# ScoutMakes_FM_Kit.net
KiCad netlist of a schematic drawn in EAGLE
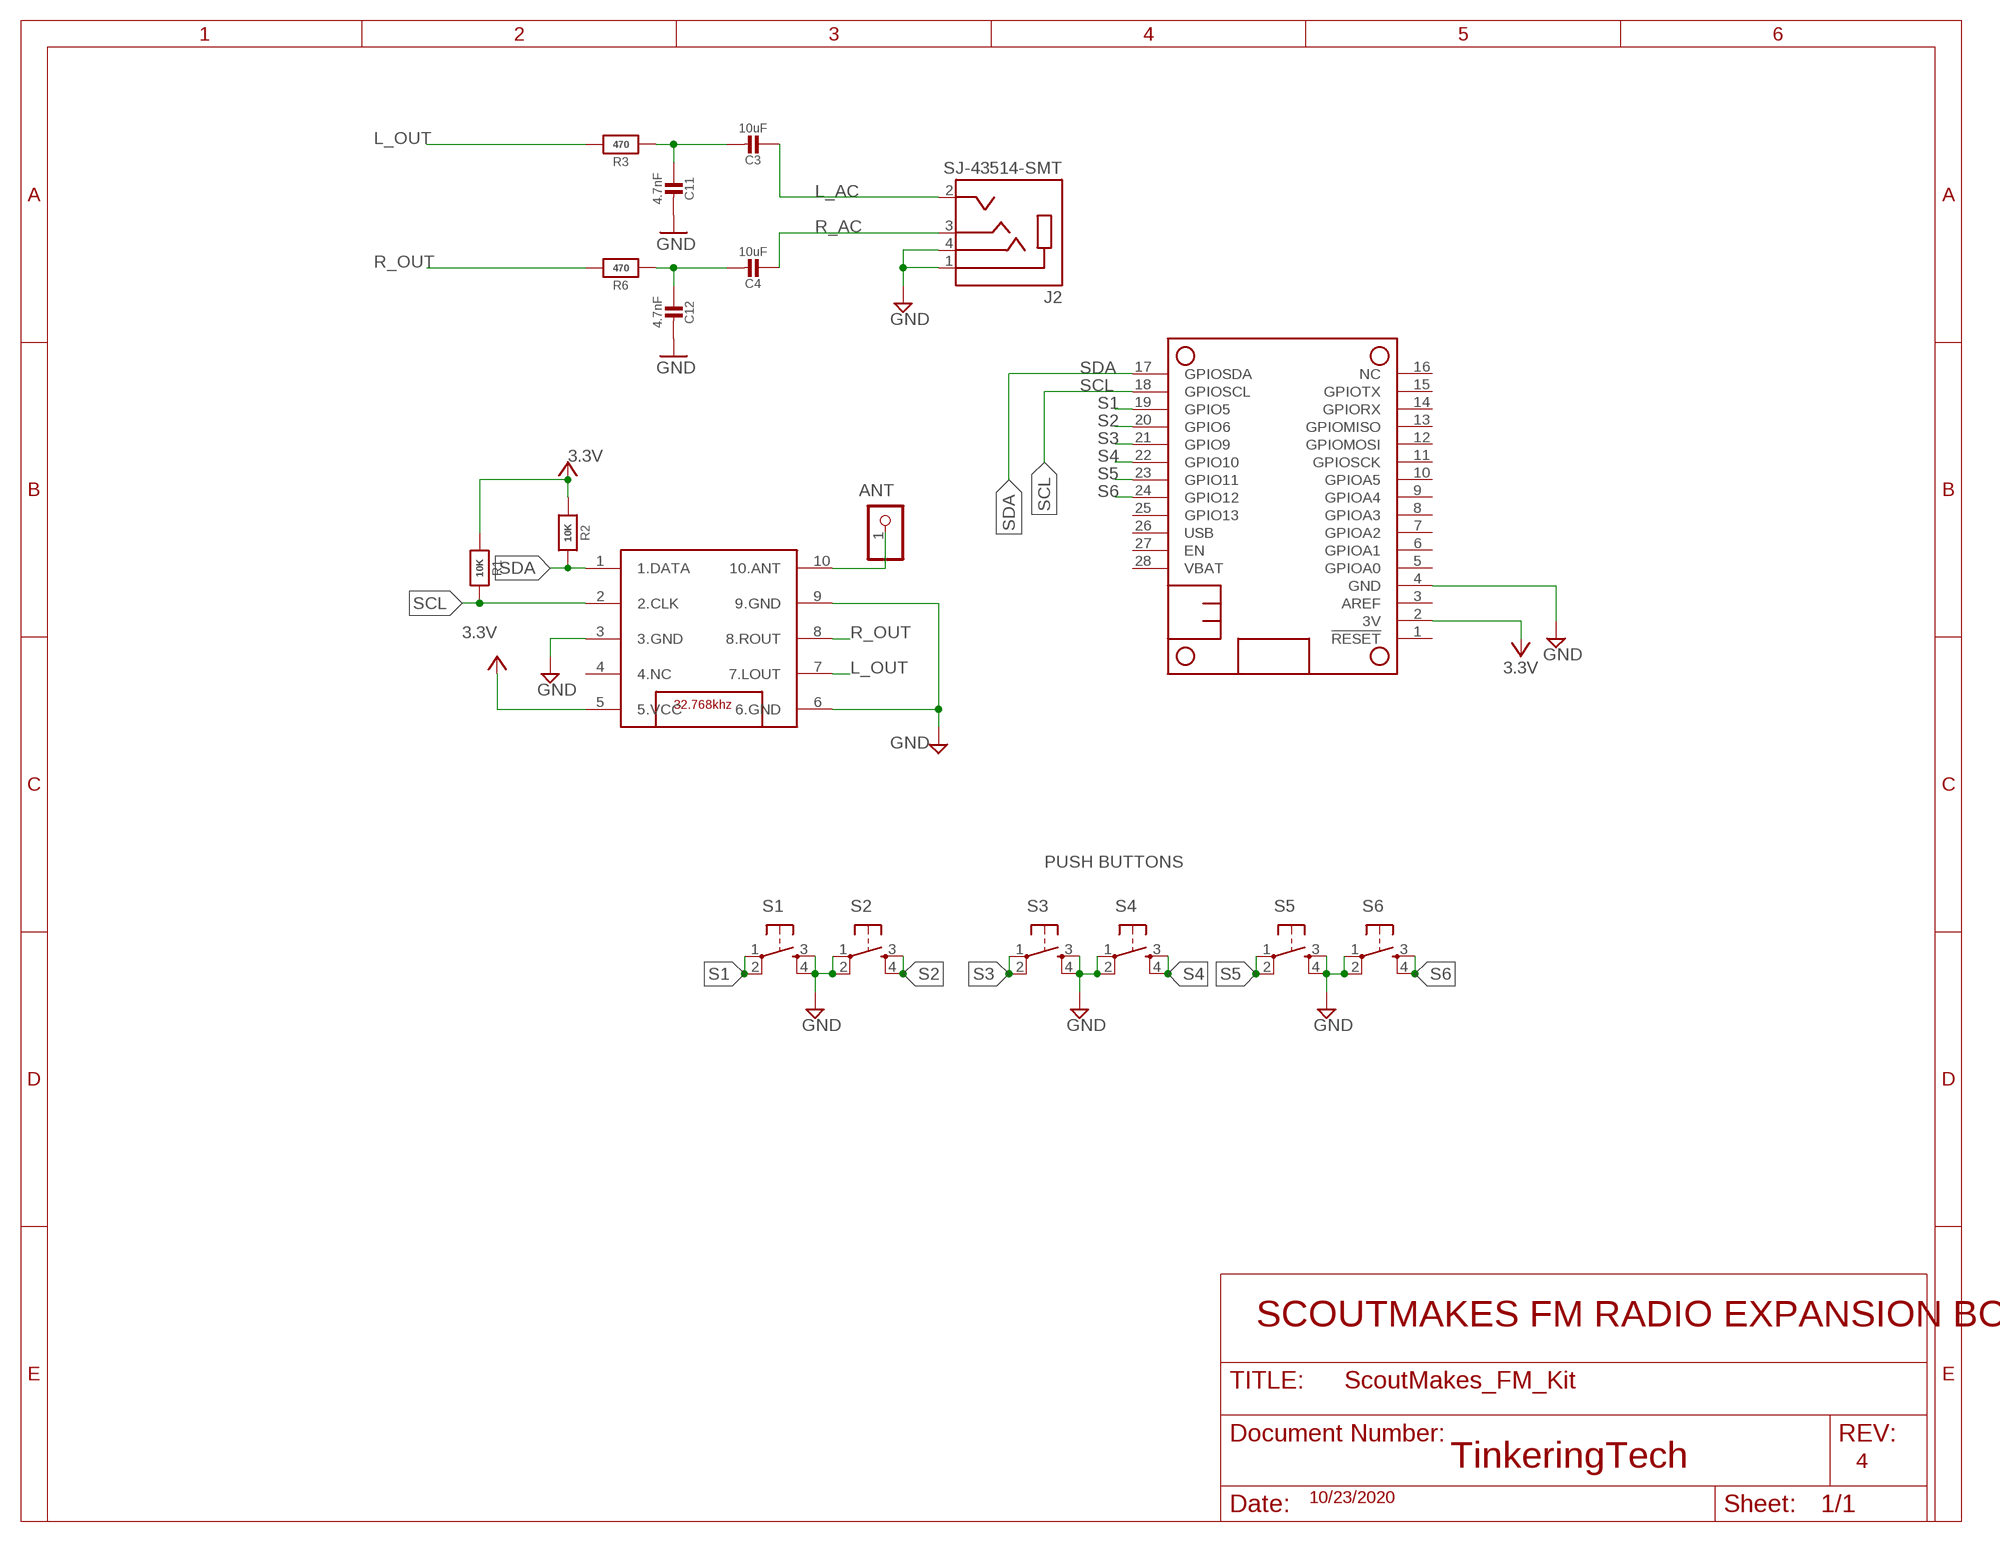
[diagram p0: schematic, sheet 1]

(export (version "E")
  (design (tool "Eeschema 10.0.6"))
  (components
    (comp (ref "ANT")
      (value "PINHD-1X1")
      (footprint "eagle-import:1X01")
      (libsource (lib "eagle-import") (part "PINHD-1X1"))
    )
    (comp (ref "C3")
      (value "10uF")
      (footprint "eagle-import:0805-NO")
      (libsource (lib "eagle-import") (part "CAP_CERAMIC0805-NOOUTLINE"))
    )
    (comp (ref "C4")
      (value "10uF")
      (footprint "eagle-import:0805-NO")
      (libsource (lib "eagle-import") (part "CAP_CERAMIC0805-NOOUTLINE"))
    )
    (comp (ref "C11")
      (value "4.7nF")
      (footprint "eagle-import:0805-NO")
      (libsource (lib "eagle-import") (part "CAP_CERAMIC0805-NOOUTLINE"))
    )
    (comp (ref "C12")
      (value "4.7nF")
      (footprint "eagle-import:0805-NO")
      (libsource (lib "eagle-import") (part "CAP_CERAMIC0805-NOOUTLINE"))
    )
    (comp (ref "J2")
      (value "SJ-43514-SMT")
      (footprint "eagle-import:CUI_SJ-43514-SMT")
      (fields
        (field (name "DIGI-KEY_PART_NUMBER") "CP-43514SJCT-ND")
        (field (name "MF") "CUI Devices")
        (field (name "MP") "SJ-43514-SMT-TR")
      )
      (libsource (lib "eagle-import") (part "SJ-43514-SMT"))
    )
    (comp (ref "MS2")
      (value "FEATHERWING_NODIM")
      (footprint "eagle-import:FEATHERWING_DIM")
      (libsource (lib "eagle-import") (part "FEATHERWING_NODIM"))
    )
    (comp (ref "R1")
      (value "10K")
      (footprint "eagle-import:0603-NO")
      (libsource (lib "eagle-import") (part "RESISTOR_0603_NOOUT"))
    )
    (comp (ref "R2")
      (value "10K")
      (footprint "eagle-import:0603-NO")
      (libsource (lib "eagle-import") (part "RESISTOR_0603_NOOUT"))
    )
    (comp (ref "R3")
      (value "470")
      (footprint "eagle-import:0805-NO")
      (libsource (lib "eagle-import") (part "RESISTOR0805_NOOUTLINE"))
    )
    (comp (ref "R6")
      (value "470")
      (footprint "eagle-import:0805-NO")
      (libsource (lib "eagle-import") (part "RESISTOR0805_NOOUTLINE"))
    )
    (comp (ref "S1")
      (value "DTS-6")
      (footprint "eagle-import:DTS-6")
      (libsource (lib "eagle-import") (part "DTS-6"))
    )
    (comp (ref "S2")
      (value "DTS-6")
      (footprint "eagle-import:DTS-6")
      (libsource (lib "eagle-import") (part "DTS-6"))
    )
    (comp (ref "S3")
      (value "DTS-6")
      (footprint "eagle-import:DTS-6")
      (libsource (lib "eagle-import") (part "DTS-6"))
    )
    (comp (ref "S4")
      (value "DTS-6")
      (footprint "eagle-import:DTS-6")
      (libsource (lib "eagle-import") (part "DTS-6"))
    )
    (comp (ref "S5")
      (value "DTS-6")
      (footprint "eagle-import:DTS-6")
      (libsource (lib "eagle-import") (part "DTS-6"))
    )
    (comp (ref "S6")
      (value "DTS-6")
      (footprint "eagle-import:DTS-6")
      (libsource (lib "eagle-import") (part "DTS-6"))
    )
    (comp (ref "U1")
      (value "TEA5767")
      (footprint "eagle-import:TJ-102BC")
      (libsource (lib "eagle-import") (part "TEA5767"))
    )
  )
  (nets
    (net (code "1") (name "/L_AC") (class "Default")
      (node (ref "C3") (pin "1") (pinfunction "1_1") (pintype "passive"))
      (node (ref "J2") (pin "2") (pinfunction "TIP_2") (pintype "passive"))
    )
    (net (code "2") (name "/L_OUT") (class "Default")
      (node (ref "R3") (pin "1") (pinfunction "1_1") (pintype "passive"))
      (node (ref "U1") (pin "7") (pinfunction "7.LOUT_7") (pintype "bidirectional"))
    )
    (net (code "3") (name "/R_AC") (class "Default")
      (node (ref "C4") (pin "1") (pinfunction "1_1") (pintype "passive"))
      (node (ref "J2") (pin "3") (pinfunction "RING1_3") (pintype "passive"))
    )
    (net (code "4") (name "/R_OUT") (class "Default")
      (node (ref "R6") (pin "1") (pinfunction "1_1") (pintype "passive"))
      (node (ref "U1") (pin "8") (pinfunction "8.ROUT_8") (pintype "bidirectional"))
    )
    (net (code "5") (name "/USB") (class "Default")
      (node (ref "MS2") (pin "26") (pinfunction "USB_26") (pintype "power_in"))
    )
    (net (code "6") (name "/VBAT") (class "Default")
      (node (ref "MS2") (pin "28") (pinfunction "VBAT_28") (pintype "power_in"))
    )
    (net (code "7") (name "3.3V") (class "Default")
      (node (ref "MS2") (pin "2") (pinfunction "3V_2") (pintype "power_in"))
      (node (ref "R1") (pin "1") (pinfunction "1_1") (pintype "passive"))
      (node (ref "R2") (pin "1") (pinfunction "1_1") (pintype "passive"))
      (node (ref "U1") (pin "5") (pinfunction "5.VCC_5") (pintype "bidirectional"))
    )
    (net (code "8") (name "GND") (class "Default")
      (node (ref "C11") (pin "2") (pinfunction "2_2") (pintype "passive"))
      (node (ref "C12") (pin "2") (pinfunction "2_2") (pintype "passive"))
      (node (ref "J2") (pin "1") (pinfunction "SLEEVE_1") (pintype "passive"))
      (node (ref "J2") (pin "4") (pinfunction "RING2_4") (pintype "passive"))
      (node (ref "MS2") (pin "4") (pinfunction "GND_4") (pintype "power_in"))
      (node (ref "S1") (pin "3") (pinfunction "3_3") (pintype "passive"))
      (node (ref "S1") (pin "4") (pinfunction "4_4") (pintype "passive"))
      (node (ref "S2") (pin "1") (pinfunction "1_1") (pintype "passive"))
      (node (ref "S2") (pin "2") (pinfunction "2_2") (pintype "passive"))
      (node (ref "S3") (pin "3") (pinfunction "3_3") (pintype "passive"))
      (node (ref "S3") (pin "4") (pinfunction "4_4") (pintype "passive"))
      (node (ref "S4") (pin "1") (pinfunction "1_1") (pintype "passive"))
      (node (ref "S4") (pin "2") (pinfunction "2_2") (pintype "passive"))
      (node (ref "S5") (pin "3") (pinfunction "3_3") (pintype "passive"))
      (node (ref "S5") (pin "4") (pinfunction "4_4") (pintype "passive"))
      (node (ref "S6") (pin "1") (pinfunction "1_1") (pintype "passive"))
      (node (ref "S6") (pin "2") (pinfunction "2_2") (pintype "passive"))
      (node (ref "U1") (pin "3") (pinfunction "3.GND_3") (pintype "bidirectional"))
      (node (ref "U1") (pin "6") (pinfunction "6.GND_6") (pintype "bidirectional"))
      (node (ref "U1") (pin "9") (pinfunction "9.GND_9") (pintype "bidirectional"))
    )
    (net (code "9") (name "Net-(C11-Pad1)") (class "Default")
      (node (ref "C11") (pin "1") (pinfunction "1_1") (pintype "passive"))
      (node (ref "C3") (pin "2") (pinfunction "2_2") (pintype "passive"))
      (node (ref "R3") (pin "2") (pinfunction "2_2") (pintype "passive"))
    )
    (net (code "10") (name "Net-(C12-Pad1)") (class "Default")
      (node (ref "C12") (pin "1") (pinfunction "1_1") (pintype "passive"))
      (node (ref "C4") (pin "2") (pinfunction "2_2") (pintype "passive"))
      (node (ref "R6") (pin "2") (pinfunction "2_2") (pintype "passive"))
    )
    (net (code "11") (name "Net-(U1-10.ANT)") (class "Default")
      (node (ref "ANT") (pin "1") (pinfunction "1_1") (pintype "passive"))
      (node (ref "U1") (pin "10") (pinfunction "10.ANT_10") (pintype "bidirectional"))
    )
    (net (code "12") (name "S1") (class "Default")
      (node (ref "MS2") (pin "19") (pinfunction "GPIO5_19") (pintype "bidirectional"))
      (node (ref "S1") (pin "1") (pinfunction "1_1") (pintype "passive"))
      (node (ref "S1") (pin "2") (pinfunction "2_2") (pintype "passive"))
    )
    (net (code "13") (name "S2") (class "Default")
      (node (ref "MS2") (pin "20") (pinfunction "GPIO6_20") (pintype "bidirectional"))
      (node (ref "S2") (pin "3") (pinfunction "3_3") (pintype "passive"))
      (node (ref "S2") (pin "4") (pinfunction "4_4") (pintype "passive"))
    )
    (net (code "14") (name "S3") (class "Default")
      (node (ref "MS2") (pin "21") (pinfunction "GPIO9_21") (pintype "bidirectional"))
      (node (ref "S3") (pin "1") (pinfunction "1_1") (pintype "passive"))
      (node (ref "S3") (pin "2") (pinfunction "2_2") (pintype "passive"))
    )
    (net (code "15") (name "S4") (class "Default")
      (node (ref "MS2") (pin "22") (pinfunction "GPIO10_22") (pintype "bidirectional"))
      (node (ref "S4") (pin "3") (pinfunction "3_3") (pintype "passive"))
      (node (ref "S4") (pin "4") (pinfunction "4_4") (pintype "passive"))
    )
    (net (code "16") (name "S5") (class "Default")
      (node (ref "MS2") (pin "23") (pinfunction "GPIO11_23") (pintype "bidirectional"))
      (node (ref "S5") (pin "1") (pinfunction "1_1") (pintype "passive"))
      (node (ref "S5") (pin "2") (pinfunction "2_2") (pintype "passive"))
    )
    (net (code "17") (name "S6") (class "Default")
      (node (ref "MS2") (pin "24") (pinfunction "GPIO12_24") (pintype "bidirectional"))
      (node (ref "S6") (pin "3") (pinfunction "3_3") (pintype "passive"))
      (node (ref "S6") (pin "4") (pinfunction "4_4") (pintype "passive"))
    )
    (net (code "18") (name "SCL") (class "Default")
      (node (ref "MS2") (pin "18") (pinfunction "GPIOSCL_18") (pintype "bidirectional"))
      (node (ref "R1") (pin "2") (pinfunction "2_2") (pintype "passive"))
      (node (ref "U1") (pin "2") (pinfunction "2.CLK_2") (pintype "bidirectional"))
    )
    (net (code "19") (name "SDA") (class "Default")
      (node (ref "MS2") (pin "17") (pinfunction "GPIOSDA_17") (pintype "bidirectional"))
      (node (ref "R2") (pin "2") (pinfunction "2_2") (pintype "passive"))
      (node (ref "U1") (pin "1") (pinfunction "1.DATA_1") (pintype "bidirectional"))
    )
    (net (code "20") (name "unconnected-(MS2-AREF-Pad3)") (class "Default")
      (node (ref "MS2") (pin "3") (pinfunction "AREF_3") (pintype "passive"))
    )
    (net (code "21") (name "unconnected-(MS2-EN-Pad27)") (class "Default")
      (node (ref "MS2") (pin "27") (pinfunction "EN_27") (pintype "passive"))
    )
    (net (code "22") (name "unconnected-(MS2-GPIO13-Pad25)") (class "Default")
      (node (ref "MS2") (pin "25") (pinfunction "GPIO13_25") (pintype "bidirectional"))
    )
    (net (code "23") (name "unconnected-(MS2-GPIOA0-Pad5)") (class "Default")
      (node (ref "MS2") (pin "5") (pinfunction "GPIOA0_5") (pintype "bidirectional"))
    )
    (net (code "24") (name "unconnected-(MS2-GPIOA1-Pad6)") (class "Default")
      (node (ref "MS2") (pin "6") (pinfunction "GPIOA1_6") (pintype "bidirectional"))
    )
    (net (code "25") (name "unconnected-(MS2-GPIOA2-Pad7)") (class "Default")
      (node (ref "MS2") (pin "7") (pinfunction "GPIOA2_7") (pintype "bidirectional"))
    )
    (net (code "26") (name "unconnected-(MS2-GPIOA3-Pad8)") (class "Default")
      (node (ref "MS2") (pin "8") (pinfunction "GPIOA3_8") (pintype "bidirectional"))
    )
    (net (code "27") (name "unconnected-(MS2-GPIOA4-Pad9)") (class "Default")
      (node (ref "MS2") (pin "9") (pinfunction "GPIOA4_9") (pintype "bidirectional"))
    )
    (net (code "28") (name "unconnected-(MS2-GPIOA5-Pad10)") (class "Default")
      (node (ref "MS2") (pin "10") (pinfunction "GPIOA5_10") (pintype "bidirectional"))
    )
    (net (code "29") (name "unconnected-(MS2-GPIOMISO-Pad13)") (class "Default")
      (node (ref "MS2") (pin "13") (pinfunction "GPIOMISO_13") (pintype "bidirectional"))
    )
    (net (code "30") (name "unconnected-(MS2-GPIOMOSI-Pad12)") (class "Default")
      (node (ref "MS2") (pin "12") (pinfunction "GPIOMOSI_12") (pintype "bidirectional"))
    )
    (net (code "31") (name "unconnected-(MS2-GPIORX-Pad14)") (class "Default")
      (node (ref "MS2") (pin "14") (pinfunction "GPIORX_14") (pintype "bidirectional"))
    )
    (net (code "32") (name "unconnected-(MS2-GPIOSCK-Pad11)") (class "Default")
      (node (ref "MS2") (pin "11") (pinfunction "GPIOSCK_11") (pintype "bidirectional"))
    )
    (net (code "33") (name "unconnected-(MS2-GPIOTX-Pad15)") (class "Default")
      (node (ref "MS2") (pin "15") (pinfunction "GPIOTX_15") (pintype "bidirectional"))
    )
    (net (code "34") (name "unconnected-(MS2-NC-Pad16)") (class "Default")
      (node (ref "MS2") (pin "16") (pinfunction "NC_16") (pintype "passive"))
    )
    (net (code "35") (name "unconnected-(MS2-~{RESET}-Pad1)") (class "Default")
      (node (ref "MS2") (pin "1") (pinfunction "~{RESET}_1") (pintype "input"))
    )
    (net (code "36") (name "unconnected-(U1-4.NC-Pad4)") (class "Default")
      (node (ref "U1") (pin "4") (pinfunction "4.NC_4") (pintype "bidirectional"))
    )
  )
)
